# meca_2014.net
KiCad netlist of a schematic drawn in EAGLE
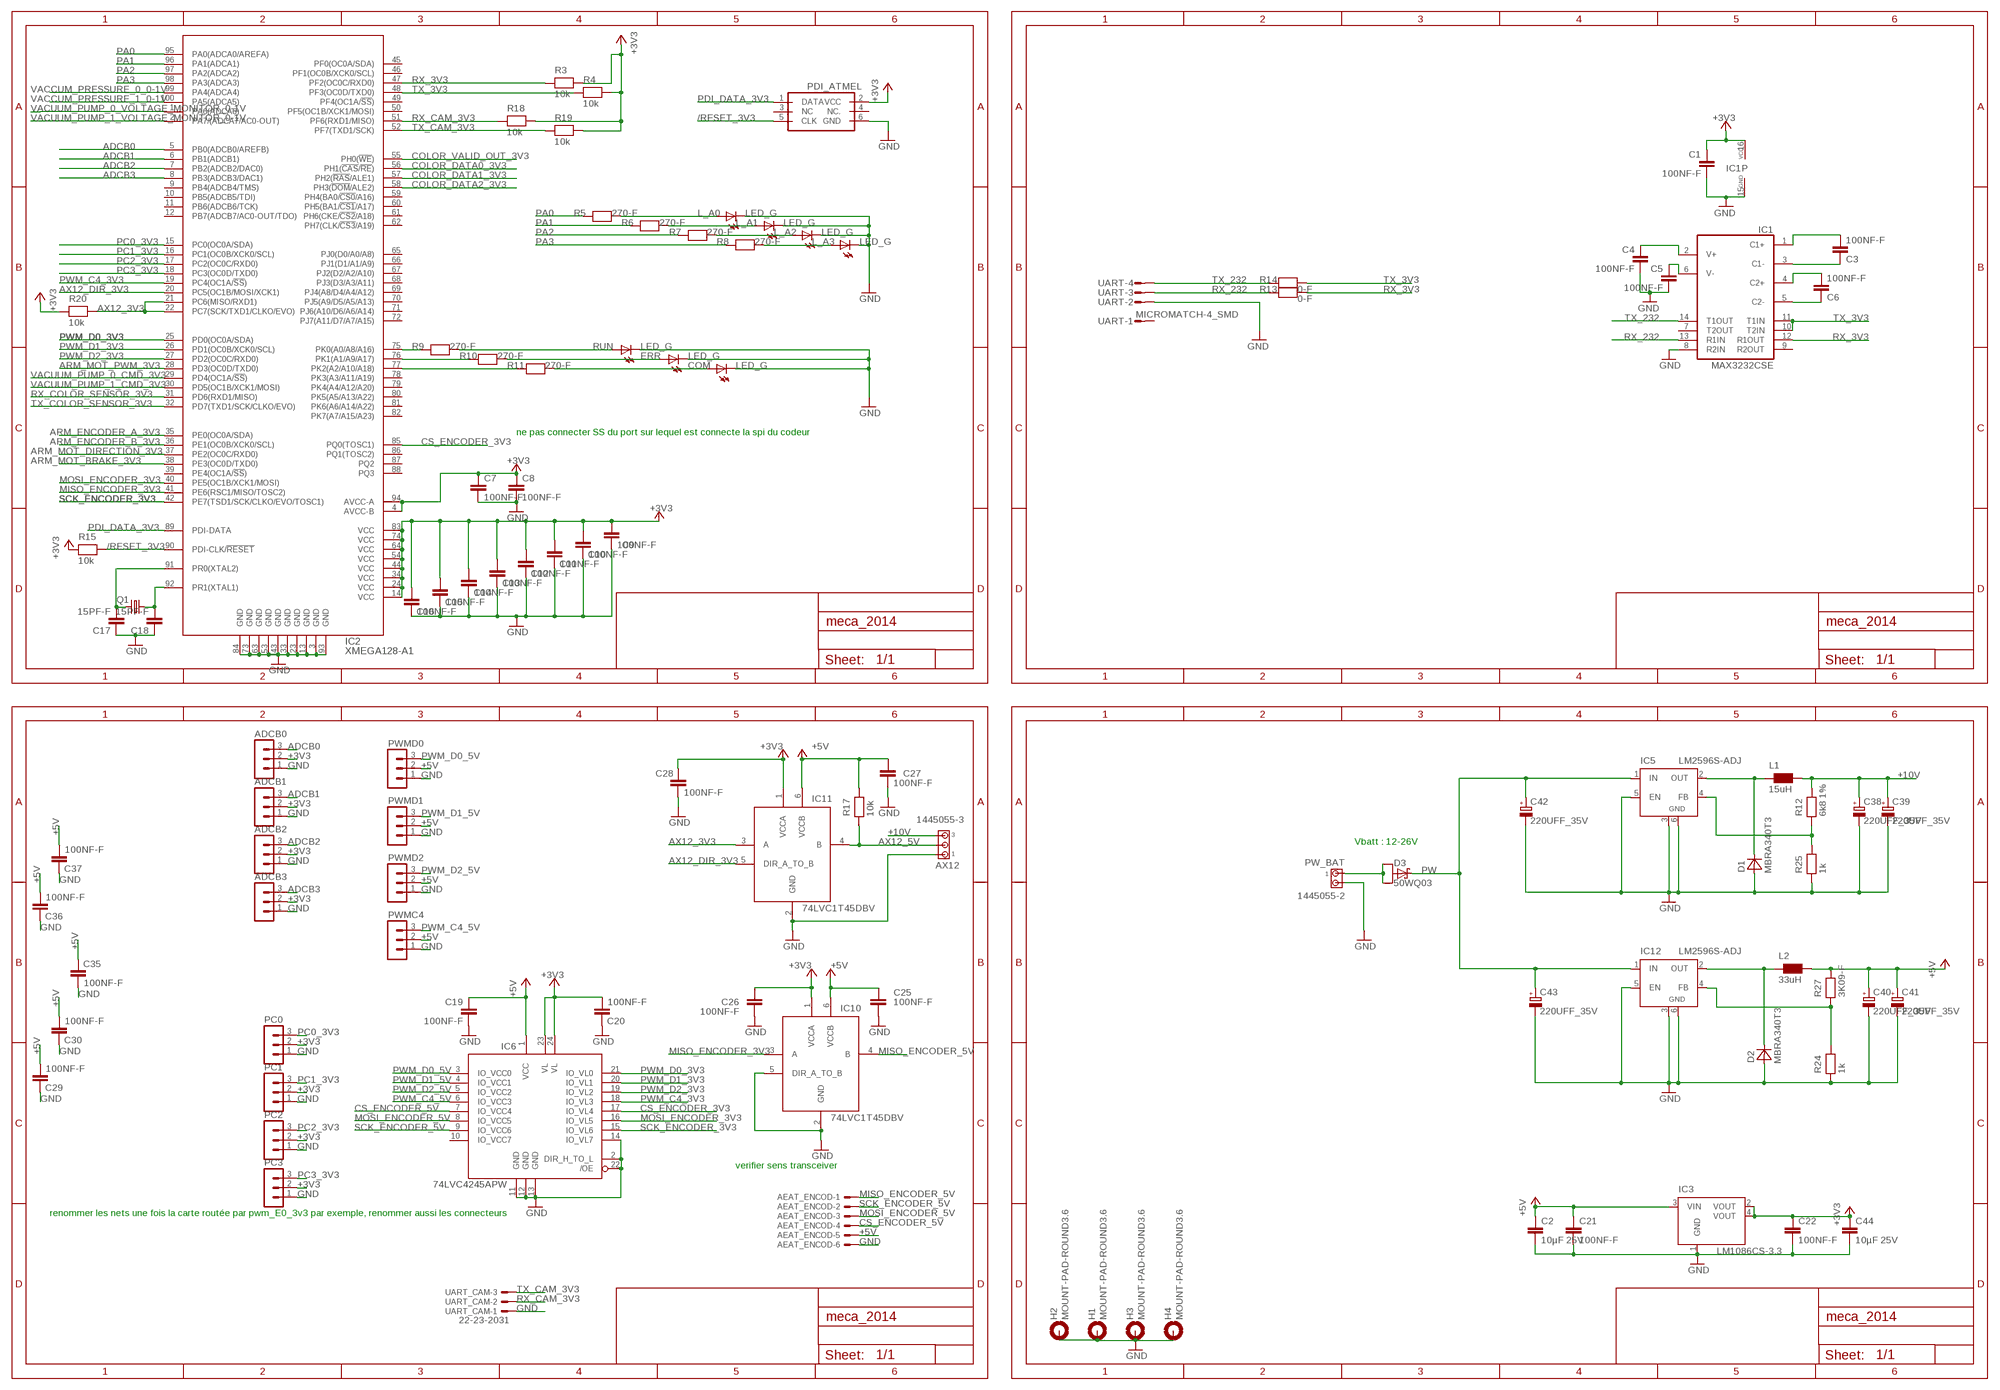
[diagram p0: schematic, sheet 1, part 1 of 2]
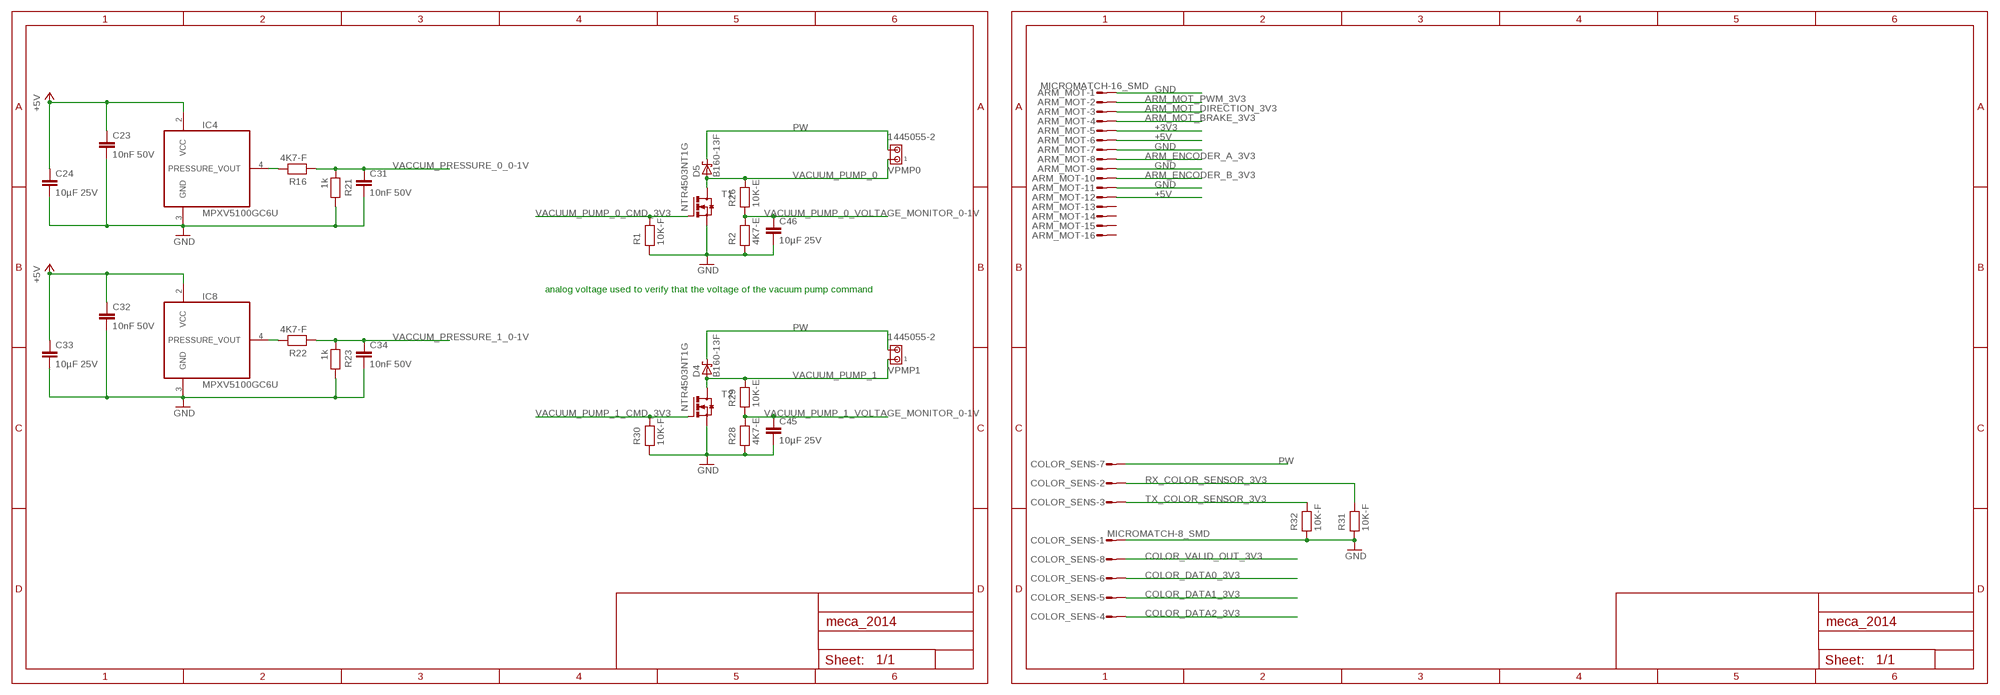
[diagram p1: schematic, sheet 1, part 2 of 2]

(export (version "E")
  (design (tool "Eeschema 10.0.6"))
  (components
    (comp (ref "ADCB0")
      (value "MA03-1")
      (footprint "eagle-import:MA03-1")
      (fields (field (name "OC_FARNELL") "unknown") (field (name "OC_NEWARK") "unknown"))
      (libsource (lib "eagle-import") (part "MA03-1"))
    )
    (comp (ref "ADCB1")
      (value "MA03-1")
      (footprint "eagle-import:MA03-1")
      (fields (field (name "OC_FARNELL") "unknown") (field (name "OC_NEWARK") "unknown"))
      (libsource (lib "eagle-import") (part "MA03-1"))
    )
    (comp (ref "ADCB2")
      (value "MA03-1")
      (footprint "eagle-import:MA03-1")
      (fields (field (name "OC_FARNELL") "unknown") (field (name "OC_NEWARK") "unknown"))
      (libsource (lib "eagle-import") (part "MA03-1"))
    )
    (comp (ref "ADCB3")
      (value "MA03-1")
      (footprint "eagle-import:MA03-1")
      (fields (field (name "OC_FARNELL") "unknown") (field (name "OC_NEWARK") "unknown"))
      (libsource (lib "eagle-import") (part "MA03-1"))
    )
    (comp (ref "AEAT_ENCOD")
      (value "22-23-2061")
      (footprint "eagle-import:22-23-2061")
      (fields (field (name "MF") "MOLEX"))
      (libsource (lib "eagle-import") (part "22-23-2061"))
    )
    (comp (ref "ARM_MOT")
      (value "MICROMATCH-16_SMD")
      (footprint "eagle-import:MICROMATCH-16_SMD")
      (libsource (lib "eagle-import") (part "MICROMATCH-16_SMD"))
    )
    (comp (ref "AX12")
      (value "1445055-3")
      (footprint "eagle-import:1445055-3")
      (libsource (lib "eagle-import") (part "1445055-3"))
    )
    (comp (ref "C1")
      (value "100NF-F")
      (footprint "eagle-import:C0603")
      (libsource (lib "eagle-import") (part "100NF-F"))
    )
    (comp (ref "C2")
      (value "10µF 25V")
      (footprint "eagle-import:C1210")
      (libsource (lib "eagle-import") (part "10UF-C_25V"))
    )
    (comp (ref "C3")
      (value "100NF-F")
      (footprint "eagle-import:C0603")
      (libsource (lib "eagle-import") (part "100NF-F"))
    )
    (comp (ref "C4")
      (value "100NF-F")
      (footprint "eagle-import:C0603")
      (libsource (lib "eagle-import") (part "100NF-F"))
    )
    (comp (ref "C5")
      (value "100NF-F")
      (footprint "eagle-import:C0603")
      (libsource (lib "eagle-import") (part "100NF-F"))
    )
    (comp (ref "C6")
      (value "100NF-F")
      (footprint "eagle-import:C0603")
      (libsource (lib "eagle-import") (part "100NF-F"))
    )
    (comp (ref "C7")
      (value "100NF-F")
      (footprint "eagle-import:C0603")
      (libsource (lib "eagle-import") (part "100NF-F"))
    )
    (comp (ref "C8")
      (value "100NF-F")
      (footprint "eagle-import:C0603")
      (libsource (lib "eagle-import") (part "100NF-F"))
    )
    (comp (ref "C9")
      (value "100NF-F")
      (footprint "eagle-import:C0603")
      (libsource (lib "eagle-import") (part "100NF-F"))
    )
    (comp (ref "C10")
      (value "100NF-F")
      (footprint "eagle-import:C0603")
      (libsource (lib "eagle-import") (part "100NF-F"))
    )
    (comp (ref "C11")
      (value "100NF-F")
      (footprint "eagle-import:C0603")
      (libsource (lib "eagle-import") (part "100NF-F"))
    )
    (comp (ref "C12")
      (value "100NF-F")
      (footprint "eagle-import:C0603")
      (libsource (lib "eagle-import") (part "100NF-F"))
    )
    (comp (ref "C13")
      (value "100NF-F")
      (footprint "eagle-import:C0603")
      (libsource (lib "eagle-import") (part "100NF-F"))
    )
    (comp (ref "C14")
      (value "100NF-F")
      (footprint "eagle-import:C0603")
      (libsource (lib "eagle-import") (part "100NF-F"))
    )
    (comp (ref "C15")
      (value "100NF-F")
      (footprint "eagle-import:C0603")
      (libsource (lib "eagle-import") (part "100NF-F"))
    )
    (comp (ref "C16")
      (value "100NF-F")
      (footprint "eagle-import:C0603")
      (libsource (lib "eagle-import") (part "100NF-F"))
    )
    (comp (ref "C17")
      (value "15PF-F")
      (footprint "eagle-import:C0603")
      (libsource (lib "eagle-import") (part "15PF-F"))
    )
    (comp (ref "C18")
      (value "15PF-F")
      (footprint "eagle-import:C0603")
      (libsource (lib "eagle-import") (part "15PF-F"))
    )
    (comp (ref "C19")
      (value "100NF-F")
      (footprint "eagle-import:C0603")
      (libsource (lib "eagle-import") (part "100NF-F"))
    )
    (comp (ref "C20")
      (value "100NF-F")
      (footprint "eagle-import:C0603")
      (libsource (lib "eagle-import") (part "100NF-F"))
    )
    (comp (ref "C21")
      (value "100NF-F")
      (footprint "eagle-import:C0603")
      (libsource (lib "eagle-import") (part "100NF-F"))
    )
    (comp (ref "C22")
      (value "100NF-F")
      (footprint "eagle-import:C0603")
      (libsource (lib "eagle-import") (part "100NF-F"))
    )
    (comp (ref "C23")
      (value "10nF 50V")
      (footprint "eagle-import:C0603")
      (libsource (lib "eagle-import") (part "10NF-F"))
    )
    (comp (ref "C24")
      (value "10µF 25V")
      (footprint "eagle-import:C1210")
      (libsource (lib "eagle-import") (part "10UF-C_25V"))
    )
    (comp (ref "C25")
      (value "100NF-F")
      (footprint "eagle-import:C0603")
      (libsource (lib "eagle-import") (part "100NF-F"))
    )
    (comp (ref "C26")
      (value "100NF-F")
      (footprint "eagle-import:C0603")
      (libsource (lib "eagle-import") (part "100NF-F"))
    )
    (comp (ref "C27")
      (value "100NF-F")
      (footprint "eagle-import:C0603")
      (libsource (lib "eagle-import") (part "100NF-F"))
    )
    (comp (ref "C28")
      (value "100NF-F")
      (footprint "eagle-import:C0603")
      (libsource (lib "eagle-import") (part "100NF-F"))
    )
    (comp (ref "C29")
      (value "100NF-F")
      (footprint "eagle-import:C0603")
      (libsource (lib "eagle-import") (part "100NF-F"))
    )
    (comp (ref "C30")
      (value "100NF-F")
      (footprint "eagle-import:C0603")
      (libsource (lib "eagle-import") (part "100NF-F"))
    )
    (comp (ref "C31")
      (value "10nF 50V")
      (footprint "eagle-import:C0603")
      (libsource (lib "eagle-import") (part "10NF-F"))
    )
    (comp (ref "C32")
      (value "10nF 50V")
      (footprint "eagle-import:C0603")
      (libsource (lib "eagle-import") (part "10NF-F"))
    )
    (comp (ref "C33")
      (value "10µF 25V")
      (footprint "eagle-import:C1210")
      (libsource (lib "eagle-import") (part "10UF-C_25V"))
    )
    (comp (ref "C34")
      (value "10nF 50V")
      (footprint "eagle-import:C0603")
      (libsource (lib "eagle-import") (part "10NF-F"))
    )
    (comp (ref "C35")
      (value "100NF-F")
      (footprint "eagle-import:C0603")
      (libsource (lib "eagle-import") (part "100NF-F"))
    )
    (comp (ref "C36")
      (value "100NF-F")
      (footprint "eagle-import:C0603")
      (libsource (lib "eagle-import") (part "100NF-F"))
    )
    (comp (ref "C37")
      (value "100NF-F")
      (footprint "eagle-import:C0603")
      (libsource (lib "eagle-import") (part "100NF-F"))
    )
    (comp (ref "C38")
      (value "220UFF_35V")
      (footprint "eagle-import:PANASONIC_F")
      (libsource (lib "eagle-import") (part "220UFF_35V"))
    )
    (comp (ref "C39")
      (value "220UFF_35V")
      (footprint "eagle-import:PANASONIC_F")
      (libsource (lib "eagle-import") (part "220UFF_35V"))
    )
    (comp (ref "C40")
      (value "220UFF_35V")
      (footprint "eagle-import:PANASONIC_F")
      (libsource (lib "eagle-import") (part "220UFF_35V"))
    )
    (comp (ref "C41")
      (value "220UFF_35V")
      (footprint "eagle-import:PANASONIC_F")
      (libsource (lib "eagle-import") (part "220UFF_35V"))
    )
    (comp (ref "C42")
      (value "220UFF_35V")
      (footprint "eagle-import:PANASONIC_F")
      (libsource (lib "eagle-import") (part "220UFF_35V"))
    )
    (comp (ref "C43")
      (value "220UFF_35V")
      (footprint "eagle-import:PANASONIC_F")
      (libsource (lib "eagle-import") (part "220UFF_35V"))
    )
    (comp (ref "C44")
      (value "10µF 25V")
      (footprint "eagle-import:C1210")
      (libsource (lib "eagle-import") (part "10UF-C_25V"))
    )
    (comp (ref "C45")
      (value "10µF 25V")
      (footprint "eagle-import:C1210")
      (libsource (lib "eagle-import") (part "10UF-C_25V"))
    )
    (comp (ref "C46")
      (value "10µF 25V")
      (footprint "eagle-import:C1210")
      (libsource (lib "eagle-import") (part "10UF-C_25V"))
    )
    (comp (ref "COLOR_SENS")
      (value "MICROMATCH-8_SMD")
      (footprint "eagle-import:MICROMATCH-8_SMD")
      (libsource (lib "eagle-import") (part "MICROMATCH-8_SMD"))
    )
    (comp (ref "COM")
      (value "LED_G")
      (footprint "eagle-import:CHIP-LED0805")
      (libsource (lib "eagle-import") (part "LED_G"))
    )
    (comp (ref "D1")
      (value "MBRA340T3")
      (footprint "eagle-import:SMA")
      (libsource (lib "eagle-import") (part "MBRA340T3"))
    )
    (comp (ref "D2")
      (value "MBRA340T3")
      (footprint "eagle-import:SMA")
      (libsource (lib "eagle-import") (part "MBRA340T3"))
    )
    (comp (ref "D3")
      (value "50WQ03")
      (footprint "eagle-import:TO252")
      (libsource (lib "eagle-import") (part "50WQ03"))
    )
    (comp (ref "D4")
      (value "B160-13F")
      (footprint "eagle-import:SMA")
      (libsource (lib "eagle-import") (part "B160-13F"))
    )
    (comp (ref "D5")
      (value "B160-13F")
      (footprint "eagle-import:SMA")
      (libsource (lib "eagle-import") (part "B160-13F"))
    )
    (comp (ref "ERR")
      (value "LED_G")
      (footprint "eagle-import:CHIP-LED0805")
      (libsource (lib "eagle-import") (part "LED_G"))
    )
    (comp (ref "H1")
      (value "MOUNT-PAD-ROUND3.6")
      (footprint "eagle-import:3,6-PAD")
      (libsource (lib "eagle-import") (part "MOUNT-PAD-ROUND3.6"))
    )
    (comp (ref "H2")
      (value "MOUNT-PAD-ROUND3.6")
      (footprint "eagle-import:3,6-PAD")
      (libsource (lib "eagle-import") (part "MOUNT-PAD-ROUND3.6"))
    )
    (comp (ref "H3")
      (value "MOUNT-PAD-ROUND3.6")
      (footprint "eagle-import:3,6-PAD")
      (libsource (lib "eagle-import") (part "MOUNT-PAD-ROUND3.6"))
    )
    (comp (ref "H4")
      (value "MOUNT-PAD-ROUND3.6")
      (footprint "eagle-import:3,6-PAD")
      (libsource (lib "eagle-import") (part "MOUNT-PAD-ROUND3.6"))
    )
    (comp (ref "IC1")
      (value "MAX3232CSE")
      (footprint "eagle-import:SO16")
      (libsource (lib "eagle-import") (part "MAX3232SEC"))
    )
    (comp (ref "IC2")
      (value "XMEGA128-A1")
      (footprint "eagle-import:TQFP100")
      (libsource (lib "eagle-import") (part "XMEGA-A1TQFP"))
    )
    (comp (ref "IC3")
      (value "LM1086CS-3.3")
      (footprint "eagle-import:TO263")
      (libsource (lib "eagle-import") (part "LM1086CS-3.3"))
    )
    (comp (ref "IC4")
      (value "MPXV5100GC6U")
      (footprint "eagle-import:482A")
      (libsource (lib "eagle-import") (part "MPXV5100GC6U"))
    )
    (comp (ref "IC5")
      (value "LM2596S-ADJ")
      (footprint "eagle-import:TO263-5")
      (libsource (lib "eagle-import") (part "LM2596S-ADJ"))
    )
    (comp (ref "IC6")
      (value "74LVC4245APW")
      (footprint "eagle-import:TSSOP24")
      (libsource (lib "eagle-import") (part "74LVC4245APW"))
    )
    (comp (ref "IC8")
      (value "MPXV5100GC6U")
      (footprint "eagle-import:482A")
      (libsource (lib "eagle-import") (part "MPXV5100GC6U"))
    )
    (comp (ref "IC10")
      (value "74LVC1T45DBV")
      (footprint "eagle-import:SOT23-6")
      (libsource (lib "eagle-import") (part "74LVC1T45DBV"))
    )
    (comp (ref "IC11")
      (value "74LVC1T45DBV")
      (footprint "eagle-import:SOT23-6")
      (libsource (lib "eagle-import") (part "74LVC1T45DBV"))
    )
    (comp (ref "IC12")
      (value "LM2596S-ADJ")
      (footprint "eagle-import:TO263-5")
      (libsource (lib "eagle-import") (part "LM2596S-ADJ"))
    )
    (comp (ref "L1")
      (value "15uH")
      (footprint "eagle-import:SRR1280")
      (libsource (lib "eagle-import") (part "SRR1280-150"))
    )
    (comp (ref "L2")
      (value "33uH")
      (footprint "eagle-import:SRR1280")
      (libsource (lib "eagle-import") (part "33µH-3.3A"))
    )
    (comp (ref "L_A0")
      (value "LED_G")
      (footprint "eagle-import:CHIP-LED0805")
      (libsource (lib "eagle-import") (part "LED_G"))
    )
    (comp (ref "L_A1")
      (value "LED_G")
      (footprint "eagle-import:CHIP-LED0805")
      (libsource (lib "eagle-import") (part "LED_G"))
    )
    (comp (ref "L_A2")
      (value "LED_G")
      (footprint "eagle-import:CHIP-LED0805")
      (libsource (lib "eagle-import") (part "LED_G"))
    )
    (comp (ref "L_A3")
      (value "LED_G")
      (footprint "eagle-import:CHIP-LED0805")
      (libsource (lib "eagle-import") (part "LED_G"))
    )
    (comp (ref "PC0")
      (value "MA03-1")
      (footprint "eagle-import:MA03-1")
      (fields (field (name "OC_FARNELL") "unknown") (field (name "OC_NEWARK") "unknown"))
      (libsource (lib "eagle-import") (part "MA03-1"))
    )
    (comp (ref "PC1")
      (value "MA03-1")
      (footprint "eagle-import:MA03-1")
      (fields (field (name "OC_FARNELL") "unknown") (field (name "OC_NEWARK") "unknown"))
      (libsource (lib "eagle-import") (part "MA03-1"))
    )
    (comp (ref "PC2")
      (value "MA03-1")
      (footprint "eagle-import:MA03-1")
      (fields (field (name "OC_FARNELL") "unknown") (field (name "OC_NEWARK") "unknown"))
      (libsource (lib "eagle-import") (part "MA03-1"))
    )
    (comp (ref "PC3")
      (value "MA03-1")
      (footprint "eagle-import:MA03-1")
      (fields (field (name "OC_FARNELL") "unknown") (field (name "OC_NEWARK") "unknown"))
      (libsource (lib "eagle-import") (part "MA03-1"))
    )
    (comp (ref "PDI_ATMEL")
      (value "PDI_ATMELL")
      (footprint "eagle-import:ML6L")
      (libsource (lib "eagle-import") (part "PDI_ATMELL"))
    )
    (comp (ref "PWMC4")
      (value "MA03-1")
      (footprint "eagle-import:MA03-1")
      (libsource (lib "eagle-import") (part "MA03-1"))
    )
    (comp (ref "PWMD0")
      (value "MA03-1")
      (footprint "eagle-import:MA03-1")
      (fields (field (name "OC_FARNELL") "unknown") (field (name "OC_NEWARK") "unknown"))
      (libsource (lib "eagle-import") (part "MA03-1"))
    )
    (comp (ref "PWMD1")
      (value "MA03-1")
      (footprint "eagle-import:MA03-1")
      (fields (field (name "OC_FARNELL") "unknown") (field (name "OC_NEWARK") "unknown"))
      (libsource (lib "eagle-import") (part "MA03-1"))
    )
    (comp (ref "PWMD2")
      (value "MA03-1")
      (footprint "eagle-import:MA03-1")
      (fields (field (name "OC_FARNELL") "unknown") (field (name "OC_NEWARK") "unknown"))
      (libsource (lib "eagle-import") (part "MA03-1"))
    )
    (comp (ref "PW_BAT")
      (value "1445055-2")
      (footprint "eagle-import:1445055-2")
      (libsource (lib "eagle-import") (part "1445055-2"))
    )
    (comp (ref "Q1")
      (value "CRYSTAL_16MHZ_HC49UP")
      (footprint "eagle-import:HC49UP")
      (libsource (lib "eagle-import") (part "CRYSTAL_16MHZ_HC49UP"))
    )
    (comp (ref "R1")
      (value "10K-F")
      (footprint "eagle-import:R0603")
      (libsource (lib "eagle-import") (part "10K-F"))
    )
    (comp (ref "R2")
      (value "4K7-E")
      (footprint "eagle-import:R0805")
      (libsource (lib "eagle-import") (part "4K7-E"))
    )
    (comp (ref "R3")
      (value "10k")
      (footprint "eagle-import:R0603")
      (libsource (lib "eagle-import") (part "10K-F"))
    )
    (comp (ref "R4")
      (value "10k")
      (footprint "eagle-import:R0603")
      (libsource (lib "eagle-import") (part "10K-F"))
    )
    (comp (ref "R5")
      (value "270-F")
      (footprint "eagle-import:R0603")
      (libsource (lib "eagle-import") (part "270-F"))
    )
    (comp (ref "R6")
      (value "270-F")
      (footprint "eagle-import:R0603")
      (libsource (lib "eagle-import") (part "270-F"))
    )
    (comp (ref "R7")
      (value "270-F")
      (footprint "eagle-import:R0603")
      (libsource (lib "eagle-import") (part "270-F"))
    )
    (comp (ref "R8")
      (value "270-F")
      (footprint "eagle-import:R0603")
      (libsource (lib "eagle-import") (part "270-F"))
    )
    (comp (ref "R9")
      (value "270-F")
      (footprint "eagle-import:R0603")
      (libsource (lib "eagle-import") (part "270-F"))
    )
    (comp (ref "R10")
      (value "270-F")
      (footprint "eagle-import:R0603")
      (libsource (lib "eagle-import") (part "270-F"))
    )
    (comp (ref "R11")
      (value "270-F")
      (footprint "eagle-import:R0603")
      (libsource (lib "eagle-import") (part "270-F"))
    )
    (comp (ref "R12")
      (value "6k8 1%")
      (footprint "eagle-import:R0603")
      (libsource (lib "eagle-import") (part "6K8-F"))
    )
    (comp (ref "R13")
      (value "0-F")
      (footprint "eagle-import:R0603")
      (libsource (lib "eagle-import") (part "0-F"))
    )
    (comp (ref "R14")
      (value "0-F")
      (footprint "eagle-import:R0603")
      (libsource (lib "eagle-import") (part "0-F"))
    )
    (comp (ref "R15")
      (value "10k")
      (footprint "eagle-import:R0603")
      (libsource (lib "eagle-import") (part "10K-F"))
    )
    (comp (ref "R16")
      (value "4K7-F")
      (footprint "eagle-import:R0603")
      (libsource (lib "eagle-import") (part "4K7-F"))
    )
    (comp (ref "R17")
      (value "10k")
      (footprint "eagle-import:R0603")
      (libsource (lib "eagle-import") (part "10K-F"))
    )
    (comp (ref "R18")
      (value "10k")
      (footprint "eagle-import:R0603")
      (libsource (lib "eagle-import") (part "10K-F"))
    )
    (comp (ref "R19")
      (value "10k")
      (footprint "eagle-import:R0603")
      (libsource (lib "eagle-import") (part "10K-F"))
    )
    (comp (ref "R20")
      (value "10k")
      (footprint "eagle-import:R0603")
      (libsource (lib "eagle-import") (part "10K-F"))
    )
    (comp (ref "R21")
      (value "1k")
      (footprint "eagle-import:R0603")
      (libsource (lib "eagle-import") (part "1K-F"))
    )
    (comp (ref "R22")
      (value "4K7-F")
      (footprint "eagle-import:R0603")
      (libsource (lib "eagle-import") (part "4K7-F"))
    )
    (comp (ref "R23")
      (value "1k")
      (footprint "eagle-import:R0603")
      (libsource (lib "eagle-import") (part "1K-F"))
    )
    (comp (ref "R24")
      (value "1k")
      (footprint "eagle-import:R0603")
      (libsource (lib "eagle-import") (part "1K-F"))
    )
    (comp (ref "R25")
      (value "1k")
      (footprint "eagle-import:R0603")
      (libsource (lib "eagle-import") (part "1K-F"))
    )
    (comp (ref "R26")
      (value "10K-E")
      (footprint "eagle-import:R0805")
      (libsource (lib "eagle-import") (part "10K-E"))
    )
    (comp (ref "R27")
      (value "3K09-F")
      (footprint "eagle-import:R0603")
      (libsource (lib "eagle-import") (part "3K09-F"))
    )
    (comp (ref "R28")
      (value "4K7-E")
      (footprint "eagle-import:R0805")
      (libsource (lib "eagle-import") (part "4K7-E"))
    )
    (comp (ref "R29")
      (value "10K-E")
      (footprint "eagle-import:R0805")
      (libsource (lib "eagle-import") (part "10K-E"))
    )
    (comp (ref "R30")
      (value "10K-F")
      (footprint "eagle-import:R0603")
      (libsource (lib "eagle-import") (part "10K-F"))
    )
    (comp (ref "R31")
      (value "10K-F")
      (footprint "eagle-import:R0603")
      (libsource (lib "eagle-import") (part "10K-F"))
    )
    (comp (ref "R32")
      (value "10K-F")
      (footprint "eagle-import:R0603")
      (libsource (lib "eagle-import") (part "10K-F"))
    )
    (comp (ref "RUN")
      (value "LED_G")
      (footprint "eagle-import:CHIP-LED0805")
      (libsource (lib "eagle-import") (part "LED_G"))
    )
    (comp (ref "T1")
      (value "NTR4503NT1G")
      (footprint "eagle-import:SOT23")
      (libsource (lib "eagle-import") (part "NTR4503NT1G"))
    )
    (comp (ref "T2")
      (value "NTR4503NT1G")
      (footprint "eagle-import:SOT23")
      (libsource (lib "eagle-import") (part "NTR4503NT1G"))
    )
    (comp (ref "UART")
      (value "MICROMATCH-4_SMD")
      (footprint "eagle-import:MICROMATCH-4_SMD")
      (libsource (lib "eagle-import") (part "MICROMATCH-4_SMD"))
    )
    (comp (ref "UART_CAM")
      (value "22-23-2031")
      (footprint "eagle-import:22-23-2031")
      (fields (field (name "MF") "MOLEX"))
      (libsource (lib "eagle-import") (part "22-23-2031"))
    )
    (comp (ref "VPMP0")
      (value "1445055-2")
      (footprint "eagle-import:1445055-2")
      (libsource (lib "eagle-import") (part "1445055-2"))
    )
    (comp (ref "VPMP1")
      (value "1445055-2")
      (footprint "eagle-import:1445055-2")
      (libsource (lib "eagle-import") (part "1445055-2"))
    )
  )
  (nets
    (net (code "1") (name "+3V3") (class "Default")
      (node (ref "ADCB0") (pin "2") (pinfunction "2_2") (pintype "passive"))
      (node (ref "ADCB1") (pin "2") (pinfunction "2_2") (pintype "passive"))
      (node (ref "ADCB2") (pin "2") (pinfunction "2_2") (pintype "passive"))
      (node (ref "ADCB3") (pin "2") (pinfunction "2_2") (pintype "passive"))
      (node (ref "ARM_MOT") (pin "5") (pinfunction "S_5") (pintype "passive"))
      (node (ref "C1") (pin "1") (pinfunction "1_1") (pintype "passive"))
      (node (ref "C10") (pin "1") (pinfunction "1_1") (pintype "passive"))
      (node (ref "C11") (pin "1") (pinfunction "1_1") (pintype "passive"))
      (node (ref "C12") (pin "1") (pinfunction "1_1") (pintype "passive"))
      (node (ref "C13") (pin "1") (pinfunction "1_1") (pintype "passive"))
      (node (ref "C14") (pin "1") (pinfunction "1_1") (pintype "passive"))
      (node (ref "C15") (pin "1") (pinfunction "1_1") (pintype "passive"))
      (node (ref "C16") (pin "1") (pinfunction "1_1") (pintype "passive"))
      (node (ref "C20") (pin "1") (pinfunction "1_1") (pintype "passive"))
      (node (ref "C22") (pin "1") (pinfunction "1_1") (pintype "passive"))
      (node (ref "C26") (pin "1") (pinfunction "1_1") (pintype "passive"))
      (node (ref "C28") (pin "1") (pinfunction "1_1") (pintype "passive"))
      (node (ref "C44") (pin "1") (pinfunction "1_1") (pintype "passive"))
      (node (ref "C7") (pin "1") (pinfunction "1_1") (pintype "passive"))
      (node (ref "C8") (pin "1") (pinfunction "1_1") (pintype "passive"))
      (node (ref "C9") (pin "1") (pinfunction "1_1") (pintype "passive"))
      (node (ref "IC1") (pin "16") (pinfunction "VCC_16") (pintype "power_in"))
      (node (ref "IC10") (pin "1") (pinfunction "VCCA_1") (pintype "power_in"))
      (node (ref "IC11") (pin "1") (pinfunction "VCCA_1") (pintype "power_in"))
      (node (ref "IC2") (pin "14") (pinfunction "VCC_14") (pintype "power_in"))
      (node (ref "IC2") (pin "24") (pinfunction "VCC_24") (pintype "power_in"))
      (node (ref "IC2") (pin "34") (pinfunction "VCC_34") (pintype "power_in"))
      (node (ref "IC2") (pin "4") (pinfunction "AVCC-B_4") (pintype "power_in"))
      (node (ref "IC2") (pin "44") (pinfunction "VCC_44") (pintype "power_in"))
      (node (ref "IC2") (pin "54") (pinfunction "VCC_54") (pintype "power_in"))
      (node (ref "IC2") (pin "64") (pinfunction "VCC_64") (pintype "power_in"))
      (node (ref "IC2") (pin "74") (pinfunction "VCC_74") (pintype "power_in"))
      (node (ref "IC2") (pin "83") (pinfunction "VCC_83") (pintype "power_in"))
      (node (ref "IC2") (pin "94") (pinfunction "AVCC-A_94") (pintype "power_in"))
      (node (ref "IC3") (pin "2") (pinfunction "VOUT_2") (pintype "bidirectional"))
      (node (ref "IC3") (pin "4") (pinfunction "VOUT_4") (pintype "bidirectional"))
      (node (ref "IC6") (pin "23") (pinfunction "VL_23") (pintype "power_in"))
      (node (ref "IC6") (pin "24") (pinfunction "VL_24") (pintype "power_in"))
      (node (ref "PC0") (pin "2") (pinfunction "2_2") (pintype "passive"))
      (node (ref "PC1") (pin "2") (pinfunction "2_2") (pintype "passive"))
      (node (ref "PC2") (pin "2") (pinfunction "2_2") (pintype "passive"))
      (node (ref "PC3") (pin "2") (pinfunction "2_2") (pintype "passive"))
      (node (ref "PDI_ATMEL") (pin "2") (pinfunction "VCC_2") (pintype "passive"))
      (node (ref "R15") (pin "1") (pinfunction "1_1") (pintype "bidirectional"))
      (node (ref "R18") (pin "2") (pinfunction "2_2") (pintype "bidirectional"))
      (node (ref "R19") (pin "2") (pinfunction "2_2") (pintype "bidirectional"))
      (node (ref "R20") (pin "1") (pinfunction "1_1") (pintype "bidirectional"))
      (node (ref "R3") (pin "2") (pinfunction "2_2") (pintype "bidirectional"))
      (node (ref "R4") (pin "2") (pinfunction "2_2") (pintype "bidirectional"))
    )
    (net (code "2") (name "+5V") (class "Default")
      (node (ref "AEAT_ENCOD") (pin "5") (pinfunction "S_5") (pintype "passive"))
      (node (ref "ARM_MOT") (pin "12") (pinfunction "S_12") (pintype "passive"))
      (node (ref "ARM_MOT") (pin "6") (pinfunction "S_6") (pintype "passive"))
      (node (ref "C19") (pin "1") (pinfunction "1_1") (pintype "passive"))
      (node (ref "C2") (pin "1") (pinfunction "1_1") (pintype "passive"))
      (node (ref "C21") (pin "1") (pinfunction "1_1") (pintype "passive"))
      (node (ref "C23") (pin "1") (pinfunction "1_1") (pintype "passive"))
      (node (ref "C24") (pin "1") (pinfunction "1_1") (pintype "passive"))
      (node (ref "C25") (pin "1") (pinfunction "1_1") (pintype "passive"))
      (node (ref "C27") (pin "1") (pinfunction "1_1") (pintype "passive"))
      (node (ref "C29") (pin "1") (pinfunction "1_1") (pintype "passive"))
      (node (ref "C30") (pin "1") (pinfunction "1_1") (pintype "passive"))
      (node (ref "C32") (pin "1") (pinfunction "1_1") (pintype "passive"))
      (node (ref "C33") (pin "1") (pinfunction "1_1") (pintype "passive"))
      (node (ref "C35") (pin "1") (pinfunction "1_1") (pintype "passive"))
      (node (ref "C36") (pin "1") (pinfunction "1_1") (pintype "passive"))
      (node (ref "C37") (pin "1") (pinfunction "1_1") (pintype "passive"))
      (node (ref "C40") (pin "+") (pinfunction "+_+") (pintype "passive"))
      (node (ref "C41") (pin "+") (pinfunction "+_+") (pintype "passive"))
      (node (ref "IC10") (pin "6") (pinfunction "VCCB_6") (pintype "power_in"))
      (node (ref "IC11") (pin "6") (pinfunction "VCCB_6") (pintype "power_in"))
      (node (ref "IC3") (pin "3") (pinfunction "VIN_3") (pintype "bidirectional"))
      (node (ref "IC4") (pin "2") (pinfunction "VCC_2") (pintype "bidirectional"))
      (node (ref "IC6") (pin "1") (pinfunction "VCC_1") (pintype "power_in"))
      (node (ref "IC8") (pin "2") (pinfunction "VCC_2") (pintype "bidirectional"))
      (node (ref "L2") (pin "2") (pinfunction "2_2") (pintype "passive"))
      (node (ref "PWMC4") (pin "2") (pinfunction "2_2") (pintype "passive"))
      (node (ref "PWMD0") (pin "2") (pinfunction "2_2") (pintype "passive"))
      (node (ref "PWMD1") (pin "2") (pinfunction "2_2") (pintype "passive"))
      (node (ref "PWMD2") (pin "2") (pinfunction "2_2") (pintype "passive"))
      (node (ref "R17") (pin "2") (pinfunction "2_2") (pintype "bidirectional"))
      (node (ref "R27") (pin "2") (pinfunction "2_2") (pintype "bidirectional"))
    )
    (net (code "3") (name "/+10V") (class "Default")
      (node (ref "AX12") (pin "3") (pinfunction "3_3") (pintype "passive"))
      (node (ref "C38") (pin "+") (pinfunction "+_+") (pintype "passive"))
      (node (ref "C39") (pin "+") (pinfunction "+_+") (pintype "passive"))
      (node (ref "L1") (pin "2") (pinfunction "2_2") (pintype "passive"))
      (node (ref "R12") (pin "2") (pinfunction "2_2") (pintype "bidirectional"))
    )
    (net (code "4") (name "/ADCB0") (class "Default")
      (node (ref "ADCB0") (pin "3") (pinfunction "3_3") (pintype "passive"))
      (node (ref "IC2") (pin "5") (pinfunction "PB0(ADCB0/AREFB)_5") (pintype "bidirectional"))
    )
    (net (code "5") (name "/ADCB1") (class "Default")
      (node (ref "ADCB1") (pin "3") (pinfunction "3_3") (pintype "passive"))
      (node (ref "IC2") (pin "6") (pinfunction "PB1(ADCB1)_6") (pintype "bidirectional"))
    )
    (net (code "6") (name "/ADCB2") (class "Default")
      (node (ref "ADCB2") (pin "3") (pinfunction "3_3") (pintype "passive"))
      (node (ref "IC2") (pin "7") (pinfunction "PB2(ADCB2/DAC0)_7") (pintype "bidirectional"))
    )
    (net (code "7") (name "/ADCB3") (class "Default")
      (node (ref "ADCB3") (pin "3") (pinfunction "3_3") (pintype "passive"))
      (node (ref "IC2") (pin "8") (pinfunction "PB3(ADCB3/DAC1)_8") (pintype "bidirectional"))
    )
    (net (code "8") (name "/ARM_ENCODER_A_3V3") (class "Default")
      (node (ref "ARM_MOT") (pin "8") (pinfunction "S_8") (pintype "passive"))
      (node (ref "IC2") (pin "35") (pinfunction "PE0(OC0A/SDA)_35") (pintype "bidirectional"))
    )
    (net (code "9") (name "/ARM_ENCODER_B_3V3") (class "Default")
      (node (ref "ARM_MOT") (pin "10") (pinfunction "S_10") (pintype "passive"))
      (node (ref "IC2") (pin "36") (pinfunction "PE1(OC0B/XCK0/SCL)_36") (pintype "bidirectional"))
    )
    (net (code "10") (name "/ARM_MOT_BRAKE_3V3") (class "Default")
      (node (ref "ARM_MOT") (pin "4") (pinfunction "S_4") (pintype "passive"))
      (node (ref "IC2") (pin "38") (pinfunction "PE3(OC0D/TXD0)_38") (pintype "bidirectional"))
    )
    (net (code "11") (name "/ARM_MOT_DIRECTION_3V3") (class "Default")
      (node (ref "ARM_MOT") (pin "3") (pinfunction "S_3") (pintype "passive"))
      (node (ref "IC2") (pin "37") (pinfunction "PE2(OC0C/RXD0)_37") (pintype "bidirectional"))
    )
    (net (code "12") (name "/ARM_MOT_PWM_3V3") (class "Default")
      (node (ref "ARM_MOT") (pin "2") (pinfunction "S_2") (pintype "passive"))
      (node (ref "IC2") (pin "28") (pinfunction "PD3(OC0D/TXD0)_28") (pintype "bidirectional"))
    )
    (net (code "13") (name "/AX12_3V3") (class "Default")
      (node (ref "IC11") (pin "3") (pinfunction "A_3") (pintype "bidirectional"))
      (node (ref "IC2") (pin "21") (pinfunction "PC6(MISO/RXD1)_21") (pintype "bidirectional"))
      (node (ref "IC2") (pin "22") (pinfunction "PC7(SCK/TXD1/CLKO/EVO)_22") (pintype "bidirectional"))
      (node (ref "R20") (pin "2") (pinfunction "2_2") (pintype "bidirectional"))
    )
    (net (code "14") (name "/AX12_5V") (class "Default")
      (node (ref "AX12") (pin "2") (pinfunction "2_2") (pintype "passive"))
      (node (ref "IC11") (pin "4") (pinfunction "B_4") (pintype "bidirectional"))
      (node (ref "R17") (pin "1") (pinfunction "1_1") (pintype "bidirectional"))
    )
    (net (code "15") (name "/AX12_DIR_3V3") (class "Default")
      (node (ref "IC11") (pin "5") (pinfunction "DIR_A_TO_B_5") (pintype "bidirectional"))
      (node (ref "IC2") (pin "20") (pinfunction "PC5(OC1B/MOSI/XCK1)_20") (pintype "bidirectional"))
    )
    (net (code "16") (name "/COLOR_DATA0_3V3") (class "Default")
      (node (ref "COLOR_SENS") (pin "6") (pinfunction "S_6") (pintype "passive"))
      (node (ref "IC2") (pin "56") (pinfunction "PH1(~{CAS}/~{RE})_56") (pintype "bidirectional"))
    )
    (net (code "17") (name "/COLOR_DATA1_3V3") (class "Default")
      (node (ref "COLOR_SENS") (pin "5") (pinfunction "S_5") (pintype "passive"))
      (node (ref "IC2") (pin "57") (pinfunction "PH2(~{RAS}/ALE1)_57") (pintype "bidirectional"))
    )
    (net (code "18") (name "/COLOR_DATA2_3V3") (class "Default")
      (node (ref "COLOR_SENS") (pin "4") (pinfunction "S_4") (pintype "passive"))
      (node (ref "IC2") (pin "58") (pinfunction "PH3(~{DOM}/ALE2)_58") (pintype "bidirectional"))
    )
    (net (code "19") (name "/COLOR_VALID_OUT_3V3") (class "Default")
      (node (ref "COLOR_SENS") (pin "8") (pinfunction "S_8") (pintype "passive"))
      (node (ref "IC2") (pin "55") (pinfunction "PH0(~{WE})_55") (pintype "bidirectional"))
    )
    (net (code "20") (name "/CS_ENCODER_3V3") (class "Default")
      (node (ref "IC2") (pin "85") (pinfunction "PQ0(TOSC1)_85") (pintype "bidirectional"))
      (node (ref "IC6") (pin "17") (pinfunction "IO_VL4_17") (pintype "bidirectional"))
    )
    (net (code "21") (name "/CS_ENCODER_5V") (class "Default")
      (node (ref "AEAT_ENCOD") (pin "4") (pinfunction "S_4") (pintype "passive"))
      (node (ref "IC6") (pin "7") (pinfunction "IO_VCC4_7") (pintype "bidirectional"))
    )
    (net (code "22") (name "/MISO_ENCODER_3V3") (class "Default")
      (node (ref "IC10") (pin "3") (pinfunction "A_3") (pintype "bidirectional"))
      (node (ref "IC2") (pin "41") (pinfunction "PE6(RSC1/MISO/TOSC2)_41") (pintype "bidirectional"))
    )
    (net (code "23") (name "/MISO_ENCODER_5V") (class "Default")
      (node (ref "AEAT_ENCOD") (pin "1") (pinfunction "S_1") (pintype "passive"))
      (node (ref "IC10") (pin "4") (pinfunction "B_4") (pintype "bidirectional"))
    )
    (net (code "24") (name "/MOSI_ENCODER_3V3") (class "Default")
      (node (ref "IC2") (pin "40") (pinfunction "PE5(OC1B/XCK1/MOSI)_40") (pintype "bidirectional"))
      (node (ref "IC6") (pin "16") (pinfunction "IO_VL5_16") (pintype "bidirectional"))
    )
    (net (code "25") (name "/MOSI_ENCODER_5V") (class "Default")
      (node (ref "AEAT_ENCOD") (pin "3") (pinfunction "S_3") (pintype "passive"))
      (node (ref "IC6") (pin "8") (pinfunction "IO_VCC5_8") (pintype "bidirectional"))
    )
    (net (code "26") (name "/PA0") (class "Default")
      (node (ref "IC2") (pin "95") (pinfunction "PA0(ADCA0/AREFA)_95") (pintype "bidirectional"))
      (node (ref "R5") (pin "1") (pinfunction "1_1") (pintype "bidirectional"))
    )
    (net (code "27") (name "/PA1") (class "Default")
      (node (ref "IC2") (pin "96") (pinfunction "PA1(ADCA1)_96") (pintype "bidirectional"))
      (node (ref "R6") (pin "1") (pinfunction "1_1") (pintype "bidirectional"))
    )
    (net (code "28") (name "/PA2") (class "Default")
      (node (ref "IC2") (pin "97") (pinfunction "PA2(ADCA2)_97") (pintype "bidirectional"))
      (node (ref "R7") (pin "1") (pinfunction "1_1") (pintype "bidirectional"))
    )
    (net (code "29") (name "/PA3") (class "Default")
      (node (ref "IC2") (pin "98") (pinfunction "PA3(ADCA3)_98") (pintype "bidirectional"))
      (node (ref "R8") (pin "1") (pinfunction "1_1") (pintype "bidirectional"))
    )
    (net (code "30") (name "/PC0_3V3") (class "Default")
      (node (ref "IC2") (pin "15") (pinfunction "PC0(OC0A/SDA)_15") (pintype "bidirectional"))
      (node (ref "PC0") (pin "3") (pinfunction "3_3") (pintype "passive"))
    )
    (net (code "31") (name "/PC1_3V3") (class "Default")
      (node (ref "IC2") (pin "16") (pinfunction "PC1(OC0B/XCK0/SCL)_16") (pintype "bidirectional"))
      (node (ref "PC1") (pin "3") (pinfunction "3_3") (pintype "passive"))
    )
    (net (code "32") (name "/PC2_3V3") (class "Default")
      (node (ref "IC2") (pin "17") (pinfunction "PC2(OC0C/RXD0)_17") (pintype "bidirectional"))
      (node (ref "PC2") (pin "3") (pinfunction "3_3") (pintype "passive"))
    )
    (net (code "33") (name "/PC3_3V3") (class "Default")
      (node (ref "IC2") (pin "18") (pinfunction "PC3(OC0D/TXD0)_18") (pintype "bidirectional"))
      (node (ref "PC3") (pin "3") (pinfunction "3_3") (pintype "passive"))
    )
    (net (code "34") (name "/PDI_DATA_3V3") (class "Default")
      (node (ref "IC2") (pin "89") (pinfunction "PDI-DATA_89") (pintype "bidirectional"))
      (node (ref "PDI_ATMEL") (pin "1") (pinfunction "DATA_1") (pintype "passive"))
    )
    (net (code "35") (name "/PW") (class "Default")
      (node (ref "C42") (pin "+") (pinfunction "+_+") (pintype "passive"))
      (node (ref "C43") (pin "+") (pinfunction "+_+") (pintype "passive"))
      (node (ref "COLOR_SENS") (pin "7") (pinfunction "S_7") (pintype "passive"))
      (node (ref "D3") (pin "4") (pinfunction "C_4") (pintype "passive"))
      (node (ref "D4") (pin "A") (pinfunction "C_A") (pintype "passive"))
      (node (ref "D5") (pin "A") (pinfunction "C_A") (pintype "passive"))
      (node (ref "IC12") (pin "1") (pinfunction "IN_1") (pintype "input"))
      (node (ref "IC5") (pin "1") (pinfunction "IN_1") (pintype "input"))
      (node (ref "VPMP0") (pin "2") (pinfunction "2_2") (pintype "passive"))
      (node (ref "VPMP1") (pin "2") (pinfunction "2_2") (pintype "passive"))
    )
    (net (code "36") (name "/PWM_C4_3V3") (class "Default")
      (node (ref "IC2") (pin "19") (pinfunction "PC4(OC1A/~{SS})_19") (pintype "bidirectional"))
      (node (ref "IC6") (pin "18") (pinfunction "IO_VL3_18") (pintype "bidirectional"))
    )
    (net (code "37") (name "/PWM_C4_5V") (class "Default")
      (node (ref "IC6") (pin "6") (pinfunction "IO_VCC3_6") (pintype "bidirectional"))
      (node (ref "PWMC4") (pin "3") (pinfunction "3_3") (pintype "passive"))
    )
    (net (code "38") (name "/PWM_D0_3V3") (class "Default")
      (node (ref "IC2") (pin "25") (pinfunction "PD0(OC0A/SDA)_25") (pintype "bidirectional"))
      (node (ref "IC6") (pin "21") (pinfunction "IO_VL0_21") (pintype "bidirectional"))
    )
    (net (code "39") (name "/PWM_D0_5V") (class "Default")
      (node (ref "IC6") (pin "3") (pinfunction "IO_VCC0_3") (pintype "bidirectional"))
      (node (ref "PWMD0") (pin "3") (pinfunction "3_3") (pintype "passive"))
    )
    (net (code "40") (name "/PWM_D1_3V3") (class "Default")
      (node (ref "IC2") (pin "26") (pinfunction "PD1(OC0B/XCK0/SCL)_26") (pintype "bidirectional"))
      (node (ref "IC6") (pin "20") (pinfunction "IO_VL1_20") (pintype "bidirectional"))
    )
    (net (code "41") (name "/PWM_D1_5V") (class "Default")
      (node (ref "IC6") (pin "4") (pinfunction "IO_VCC1_4") (pintype "bidirectional"))
      (node (ref "PWMD1") (pin "3") (pinfunction "3_3") (pintype "passive"))
    )
    (net (code "42") (name "/PWM_D2_3V3") (class "Default")
      (node (ref "IC2") (pin "27") (pinfunction "PD2(OC0C/RXD0)_27") (pintype "bidirectional"))
      (node (ref "IC6") (pin "19") (pinfunction "IO_VL2_19") (pintype "bidirectional"))
    )
    (net (code "43") (name "/PWM_D2_5V") (class "Default")
      (node (ref "IC6") (pin "5") (pinfunction "IO_VCC2_5") (pintype "bidirectional"))
      (node (ref "PWMD2") (pin "3") (pinfunction "3_3") (pintype "passive"))
    )
    (net (code "44") (name "/RX_3V3") (class "Default")
      (node (ref "IC1") (pin "12") (pinfunction "R1OUT_12") (pintype "output"))
      (node (ref "IC2") (pin "47") (pinfunction "PF2(OC0C/RXD0)_47") (pintype "bidirectional"))
      (node (ref "R13") (pin "2") (pinfunction "2_2") (pintype "bidirectional"))
      (node (ref "R3") (pin "1") (pinfunction "1_1") (pintype "bidirectional"))
    )
    (net (code "45") (name "/RX_232") (class "Default")
      (node (ref "IC1") (pin "13") (pinfunction "R1IN_13") (pintype "input"))
      (node (ref "R13") (pin "1") (pinfunction "1_1") (pintype "bidirectional"))
      (node (ref "UART") (pin "3") (pinfunction "S_3") (pintype "passive"))
    )
    (net (code "46") (name "/RX_CAM_3V3") (class "Default")
      (node (ref "IC2") (pin "51") (pinfunction "PF6(RXD1/MISO)_51") (pintype "bidirectional"))
      (node (ref "R18") (pin "1") (pinfunction "1_1") (pintype "bidirectional"))
      (node (ref "UART_CAM") (pin "2") (pinfunction "S_2") (pintype "passive"))
    )
    (net (code "47") (name "/RX_COLOR_SENSOR_3V3") (class "Default")
      (node (ref "COLOR_SENS") (pin "2") (pinfunction "S_2") (pintype "passive"))
      (node (ref "IC2") (pin "31") (pinfunction "PD6(RXD1/MISO)_31") (pintype "bidirectional"))
      (node (ref "R31") (pin "2") (pinfunction "2_2") (pintype "bidirectional"))
    )
    (net (code "48") (name "/SCK_ENCODER_3V3") (class "Default")
      (node (ref "IC2") (pin "42") (pinfunction "PE7(TSD1/SCK/CLKO/EVO/TOSC1)_42") (pintype "bidirectional"))
      (node (ref "IC6") (pin "15") (pinfunction "IO_VL6_15") (pintype "bidirectional"))
    )
    (net (code "49") (name "/SCK_ENCODER_5V") (class "Default")
      (node (ref "AEAT_ENCOD") (pin "2") (pinfunction "S_2") (pintype "passive"))
      (node (ref "IC6") (pin "9") (pinfunction "IO_VCC6_9") (pintype "bidirectional"))
    )
    (net (code "50") (name "/TX_3V3") (class "Default")
      (node (ref "IC1") (pin "10") (pinfunction "T2IN_10") (pintype "input"))
      (node (ref "IC1") (pin "11") (pinfunction "T1IN_11") (pintype "input"))
      (node (ref "IC2") (pin "48") (pinfunction "PF3(OC0D/TXD0)_48") (pintype "bidirectional"))
      (node (ref "R14") (pin "2") (pinfunction "2_2") (pintype "bidirectional"))
      (node (ref "R4") (pin "1") (pinfunction "1_1") (pintype "bidirectional"))
    )
    (net (code "51") (name "/TX_232") (class "Default")
      (node (ref "IC1") (pin "14") (pinfunction "T1OUT_14") (pintype "output"))
      (node (ref "R14") (pin "1") (pinfunction "1_1") (pintype "bidirectional"))
      (node (ref "UART") (pin "4") (pinfunction "S_4") (pintype "passive"))
    )
    (net (code "52") (name "/TX_CAM_3V3") (class "Default")
      (node (ref "IC2") (pin "52") (pinfunction "PF7(TXD1/SCK)_52") (pintype "bidirectional"))
      (node (ref "R19") (pin "1") (pinfunction "1_1") (pintype "bidirectional"))
      (node (ref "UART_CAM") (pin "3") (pinfunction "S_3") (pintype "passive"))
    )
    (net (code "53") (name "/TX_COLOR_SENSOR_3V3") (class "Default")
      (node (ref "COLOR_SENS") (pin "3") (pinfunction "S_3") (pintype "passive"))
      (node (ref "IC2") (pin "32") (pinfunction "PD7(TXD1/SCK/CLKO/EVO)_32") (pintype "bidirectional"))
      (node (ref "R32") (pin "2") (pinfunction "2_2") (pintype "bidirectional"))
    )
    (net (code "54") (name "/VACCUM_PRESSURE_0_0-1V") (class "Default")
      (node (ref "C31") (pin "1") (pinfunction "1_1") (pintype "passive"))
      (node (ref "IC2") (pin "99") (pinfunction "PA4(ADCA4)_99") (pintype "bidirectional"))
      (node (ref "R16") (pin "1") (pinfunction "1_1") (pintype "bidirectional"))
      (node (ref "R21") (pin "1") (pinfunction "1_1") (pintype "bidirectional"))
    )
    (net (code "55") (name "/VACCUM_PRESSURE_1_0-1V") (class "Default")
      (node (ref "C34") (pin "1") (pinfunction "1_1") (pintype "passive"))
      (node (ref "IC2") (pin "100") (pinfunction "PA5(ADCA5)_100") (pintype "bidirectional"))
      (node (ref "R22") (pin "1") (pinfunction "1_1") (pintype "bidirectional"))
      (node (ref "R23") (pin "1") (pinfunction "1_1") (pintype "bidirectional"))
    )
    (net (code "56") (name "/VACUUM_PUMP_0") (class "Default")
      (node (ref "D5") (pin "C") (pinfunction "A_C") (pintype "passive"))
      (node (ref "R26") (pin "2") (pinfunction "2_2") (pintype "bidirectional"))
      (node (ref "T1") (pin "3") (pinfunction "D_3") (pintype "passive"))
      (node (ref "VPMP0") (pin "1") (pinfunction "1_1") (pintype "passive"))
    )
    (net (code "57") (name "/VACUUM_PUMP_0_CMD_3V3") (class "Default")
      (node (ref "IC2") (pin "29") (pinfunction "PD4(OC1A/~{SS})_29") (pintype "bidirectional"))
      (node (ref "R1") (pin "2") (pinfunction "2_2") (pintype "bidirectional"))
      (node (ref "T1") (pin "1") (pinfunction "G_1") (pintype "passive"))
    )
    (net (code "58") (name "/VACUUM_PUMP_0_VOLTAGE_MONITOR_0-1V") (class "Default")
      (node (ref "C46") (pin "1") (pinfunction "1_1") (pintype "passive"))
      (node (ref "IC2") (pin "1") (pinfunction "PA6(ADCA6)_1") (pintype "bidirectional"))
      (node (ref "R2") (pin "2") (pinfunction "2_2") (pintype "bidirectional"))
      (node (ref "R26") (pin "1") (pinfunction "1_1") (pintype "bidirectional"))
    )
    (net (code "59") (name "/VACUUM_PUMP_1") (class "Default")
      (node (ref "D4") (pin "C") (pinfunction "A_C") (pintype "passive"))
      (node (ref "R29") (pin "2") (pinfunction "2_2") (pintype "bidirectional"))
      (node (ref "T2") (pin "3") (pinfunction "D_3") (pintype "passive"))
      (node (ref "VPMP1") (pin "1") (pinfunction "1_1") (pintype "passive"))
    )
    (net (code "60") (name "/VACUUM_PUMP_1_CMD_3V3") (class "Default")
      (node (ref "IC2") (pin "30") (pinfunction "PD5(OC1B/XCK1/MOSI)_30") (pintype "bidirectional"))
      (node (ref "R30") (pin "2") (pinfunction "2_2") (pintype "bidirectional"))
      (node (ref "T2") (pin "1") (pinfunction "G_1") (pintype "passive"))
    )
    (net (code "61") (name "/VACUUM_PUMP_1_VOLTAGE_MONITOR_0-1V") (class "Default")
      (node (ref "C45") (pin "1") (pinfunction "1_1") (pintype "passive"))
      (node (ref "IC2") (pin "2") (pinfunction "PA7/(ADCA7/AC0-OUT)_2") (pintype "bidirectional"))
      (node (ref "R28") (pin "2") (pinfunction "2_2") (pintype "bidirectional"))
      (node (ref "R29") (pin "1") (pinfunction "1_1") (pintype "bidirectional"))
    )
    (net (code "62") (name "/{slash}RESET_3V3") (class "Default")
      (node (ref "IC2") (pin "90") (pinfunction "PDI-CLK/~{RESET}_90") (pintype "input"))
      (node (ref "PDI_ATMEL") (pin "5") (pinfunction "CLK_5") (pintype "passive"))
      (node (ref "R15") (pin "2") (pinfunction "2_2") (pintype "bidirectional"))
    )
    (net (code "63") (name "GND") (class "Default")
      (node (ref "ADCB0") (pin "1") (pinfunction "1_1") (pintype "passive"))
      (node (ref "ADCB1") (pin "1") (pinfunction "1_1") (pintype "passive"))
      (node (ref "ADCB2") (pin "1") (pinfunction "1_1") (pintype "passive"))
      (node (ref "ADCB3") (pin "1") (pinfunction "1_1") (pintype "passive"))
      (node (ref "AEAT_ENCOD") (pin "6") (pinfunction "S_6") (pintype "passive"))
      (node (ref "ARM_MOT") (pin "1") (pinfunction "S_1") (pintype "passive"))
      (node (ref "ARM_MOT") (pin "11") (pinfunction "S_11") (pintype "passive"))
      (node (ref "ARM_MOT") (pin "7") (pinfunction "S_7") (pintype "passive"))
      (node (ref "ARM_MOT") (pin "9") (pinfunction "S_9") (pintype "passive"))
      (node (ref "AX12") (pin "1") (pinfunction "1_1") (pintype "passive"))
      (node (ref "C1") (pin "2") (pinfunction "2_2") (pintype "passive"))
      (node (ref "C10") (pin "2") (pinfunction "2_2") (pintype "passive"))
      (node (ref "C11") (pin "2") (pinfunction "2_2") (pintype "passive"))
      (node (ref "C12") (pin "2") (pinfunction "2_2") (pintype "passive"))
      (node (ref "C13") (pin "2") (pinfunction "2_2") (pintype "passive"))
      (node (ref "C14") (pin "2") (pinfunction "2_2") (pintype "passive"))
      (node (ref "C15") (pin "2") (pinfunction "2_2") (pintype "passive"))
      (node (ref "C16") (pin "2") (pinfunction "2_2") (pintype "passive"))
      (node (ref "C17") (pin "1") (pinfunction "1_1") (pintype "passive"))
      (node (ref "C18") (pin "1") (pinfunction "1_1") (pintype "passive"))
      (node (ref "C19") (pin "2") (pinfunction "2_2") (pintype "passive"))
      (node (ref "C2") (pin "2") (pinfunction "2_2") (pintype "passive"))
      (node (ref "C20") (pin "2") (pinfunction "2_2") (pintype "passive"))
      (node (ref "C21") (pin "2") (pinfunction "2_2") (pintype "passive"))
      (node (ref "C22") (pin "2") (pinfunction "2_2") (pintype "passive"))
      (node (ref "C23") (pin "2") (pinfunction "2_2") (pintype "passive"))
      (node (ref "C24") (pin "2") (pinfunction "2_2") (pintype "passive"))
      (node (ref "C25") (pin "2") (pinfunction "2_2") (pintype "passive"))
      (node (ref "C26") (pin "2") (pinfunction "2_2") (pintype "passive"))
      (node (ref "C27") (pin "2") (pinfunction "2_2") (pintype "passive"))
      (node (ref "C28") (pin "2") (pinfunction "2_2") (pintype "passive"))
      (node (ref "C29") (pin "2") (pinfunction "2_2") (pintype "passive"))
      (node (ref "C30") (pin "2") (pinfunction "2_2") (pintype "passive"))
      (node (ref "C31") (pin "2") (pinfunction "2_2") (pintype "passive"))
      (node (ref "C32") (pin "2") (pinfunction "2_2") (pintype "passive"))
      (node (ref "C33") (pin "2") (pinfunction "2_2") (pintype "passive"))
      (node (ref "C34") (pin "2") (pinfunction "2_2") (pintype "passive"))
      (node (ref "C35") (pin "2") (pinfunction "2_2") (pintype "passive"))
      (node (ref "C36") (pin "2") (pinfunction "2_2") (pintype "passive"))
      (node (ref "C37") (pin "2") (pinfunction "2_2") (pintype "passive"))
      (node (ref "C38") (pin "-") (pinfunction "-_-") (pintype "passive"))
      (node (ref "C39") (pin "-") (pinfunction "-_-") (pintype "passive"))
      (node (ref "C4") (pin "2") (pinfunction "2_2") (pintype "passive"))
      (node (ref "C40") (pin "-") (pinfunction "-_-") (pintype "passive"))
      (node (ref "C41") (pin "-") (pinfunction "-_-") (pintype "passive"))
      (node (ref "C42") (pin "-") (pinfunction "-_-") (pintype "passive"))
      (node (ref "C43") (pin "-") (pinfunction "-_-") (pintype "passive"))
      (node (ref "C44") (pin "2") (pinfunction "2_2") (pintype "passive"))
      (node (ref "C45") (pin "2") (pinfunction "2_2") (pintype "passive"))
      (node (ref "C46") (pin "2") (pinfunction "2_2") (pintype "passive"))
      (node (ref "C5") (pin "2") (pinfunction "2_2") (pintype "passive"))
      (node (ref "C7") (pin "2") (pinfunction "2_2") (pintype "passive"))
      (node (ref "C8") (pin "2") (pinfunction "2_2") (pintype "passive"))
      (node (ref "C9") (pin "2") (pinfunction "2_2") (pintype "passive"))
      (node (ref "COLOR_SENS") (pin "1") (pinfunction "S_1") (pintype "passive"))
      (node (ref "COM") (pin "C") (pinfunction "C_C") (pintype "passive"))
      (node (ref "D1") (pin "A") (pinfunction "A_A") (pintype "passive"))
      (node (ref "D2") (pin "A") (pinfunction "A_A") (pintype "passive"))
      (node (ref "ERR") (pin "C") (pinfunction "C_C") (pintype "passive"))
      (node (ref "H1") (pin "B3,6") (pinfunction "MOUNT_B3,6") (pintype "passive"))
      (node (ref "H2") (pin "B3,6") (pinfunction "MOUNT_B3,6") (pintype "passive"))
      (node (ref "H3") (pin "B3,6") (pinfunction "MOUNT_B3,6") (pintype "passive"))
      (node (ref "H4") (pin "B3,6") (pinfunction "MOUNT_B3,6") (pintype "passive"))
      (node (ref "IC1") (pin "15") (pinfunction "GND_15") (pintype "power_in"))
      (node (ref "IC1") (pin "8") (pinfunction "R2IN_8") (pintype "input"))
      (node (ref "IC10") (pin "2") (pinfunction "GND_2") (pintype "power_in"))
      (node (ref "IC10") (pin "5") (pinfunction "DIR_A_TO_B_5") (pintype "bidirectional"))
      (node (ref "IC11") (pin "2") (pinfunction "GND_2") (pintype "power_in"))
      (node (ref "IC12") (pin "3") (pinfunction "GND_3") (pintype "power_in"))
      (node (ref "IC12") (pin "5") (pinfunction "EN_5") (pintype "input"))
      (node (ref "IC12") (pin "6") (pinfunction "GND_6") (pintype "power_in"))
      (node (ref "IC2") (pin "13") (pinfunction "GND_13") (pintype "power_in"))
      (node (ref "IC2") (pin "23") (pinfunction "GND_23") (pintype "power_in"))
      (node (ref "IC2") (pin "3") (pinfunction "GND_3") (pintype "power_in"))
      (node (ref "IC2") (pin "33") (pinfunction "GND_33") (pintype "power_in"))
      (node (ref "IC2") (pin "43") (pinfunction "GND_43") (pintype "power_in"))
      (node (ref "IC2") (pin "53") (pinfunction "GND_53") (pintype "power_in"))
      (node (ref "IC2") (pin "63") (pinfunction "GND_63") (pintype "power_in"))
      (node (ref "IC2") (pin "73") (pinfunction "GND_73") (pintype "power_in"))
      (node (ref "IC2") (pin "84") (pinfunction "GND_84") (pintype "power_in"))
      (node (ref "IC2") (pin "93") (pinfunction "GND_93") (pintype "power_in"))
      (node (ref "IC3") (pin "1") (pinfunction "GND_1") (pintype "bidirectional"))
      (node (ref "IC4") (pin "3") (pinfunction "GND_3") (pintype "input"))
      (node (ref "IC5") (pin "3") (pinfunction "GND_3") (pintype "power_in"))
      (node (ref "IC5") (pin "5") (pinfunction "EN_5") (pintype "input"))
      (node (ref "IC5") (pin "6") (pinfunction "GND_6") (pintype "power_in"))
      (node (ref "IC6") (pin "11") (pinfunction "GND_11") (pintype "power_in"))
      (node (ref "IC6") (pin "12") (pinfunction "GND_12") (pintype "power_in"))
      (node (ref "IC6") (pin "13") (pinfunction "GND_13") (pintype "power_in"))
      (node (ref "IC6") (pin "14") (pinfunction "IO_VL7_14") (pintype "bidirectional"))
      (node (ref "IC6") (pin "2") (pinfunction "DIR_H_TO_L_2") (pintype "bidirectional"))
      (node (ref "IC6") (pin "22") (pinfunction "/OE_22") (pintype "bidirectional"))
      (node (ref "IC8") (pin "3") (pinfunction "GND_3") (pintype "input"))
      (node (ref "L_A0") (pin "C") (pinfunction "C_C") (pintype "passive"))
      (node (ref "L_A1") (pin "C") (pinfunction "C_C") (pintype "passive"))
      (node (ref "L_A2") (pin "C") (pinfunction "C_C") (pintype "passive"))
      (node (ref "L_A3") (pin "C") (pinfunction "C_C") (pintype "passive"))
      (node (ref "PC0") (pin "1") (pinfunction "1_1") (pintype "passive"))
      (node (ref "PC1") (pin "1") (pinfunction "1_1") (pintype "passive"))
      (node (ref "PC2") (pin "1") (pinfunction "1_1") (pintype "passive"))
      (node (ref "PC3") (pin "1") (pinfunction "1_1") (pintype "passive"))
      (node (ref "PDI_ATMEL") (pin "6") (pinfunction "GND_6") (pintype "passive"))
      (node (ref "PWMC4") (pin "1") (pinfunction "1_1") (pintype "passive"))
      (node (ref "PWMD0") (pin "1") (pinfunction "1_1") (pintype "passive"))
      (node (ref "PWMD1") (pin "1") (pinfunction "1_1") (pintype "passive"))
      (node (ref "PWMD2") (pin "1") (pinfunction "1_1") (pintype "passive"))
      (node (ref "PW_BAT") (pin "2") (pinfunction "2_2") (pintype "passive"))
      (node (ref "R1") (pin "1") (pinfunction "1_1") (pintype "bidirectional"))
      (node (ref "R2") (pin "1") (pinfunction "1_1") (pintype "bidirectional"))
      (node (ref "R21") (pin "2") (pinfunction "2_2") (pintype "bidirectional"))
      (node (ref "R23") (pin "2") (pinfunction "2_2") (pintype "bidirectional"))
      (node (ref "R24") (pin "1") (pinfunction "1_1") (pintype "bidirectional"))
      (node (ref "R25") (pin "1") (pinfunction "1_1") (pintype "bidirectional"))
      (node (ref "R28") (pin "1") (pinfunction "1_1") (pintype "bidirectional"))
      (node (ref "R30") (pin "1") (pinfunction "1_1") (pintype "bidirectional"))
      (node (ref "R31") (pin "1") (pinfunction "1_1") (pintype "bidirectional"))
      (node (ref "R32") (pin "1") (pinfunction "1_1") (pintype "bidirectional"))
      (node (ref "RUN") (pin "C") (pinfunction "C_C") (pintype "passive"))
      (node (ref "T1") (pin "2") (pinfunction "S_2") (pintype "passive"))
      (node (ref "T2") (pin "2") (pinfunction "S_2") (pintype "passive"))
      (node (ref "UART") (pin "2") (pinfunction "S_2") (pintype "passive"))
      (node (ref "UART_CAM") (pin "1") (pinfunction "S_1") (pintype "passive"))
    )
    (net (code "64") (name "Net-(COM-PadA)") (class "Default")
      (node (ref "COM") (pin "A") (pinfunction "A_A") (pintype "passive"))
      (node (ref "R11") (pin "2") (pinfunction "2_2") (pintype "bidirectional"))
    )
    (net (code "65") (name "Net-(D3-A1)") (class "Default")
      (node (ref "D3") (pin "1") (pinfunction "A1_1") (pintype "passive"))
      (node (ref "D3") (pin "3") (pinfunction "A2_3") (pintype "passive"))
      (node (ref "PW_BAT") (pin "1") (pinfunction "1_1") (pintype "passive"))
    )
    (net (code "66") (name "Net-(ERR-PadA)") (class "Default")
      (node (ref "ERR") (pin "A") (pinfunction "A_A") (pintype "passive"))
      (node (ref "R10") (pin "2") (pinfunction "2_2") (pintype "bidirectional"))
    )
    (net (code "67") (name "Net-(IC1A-C1+)") (class "Default")
      (node (ref "C3") (pin "1") (pinfunction "1_1") (pintype "passive"))
      (node (ref "IC1") (pin "1") (pinfunction "C1+_1") (pintype "bidirectional"))
    )
    (net (code "68") (name "Net-(IC1A-C1-)") (class "Default")
      (node (ref "C3") (pin "2") (pinfunction "2_2") (pintype "passive"))
      (node (ref "IC1") (pin "3") (pinfunction "C1-_3") (pintype "bidirectional"))
    )
    (net (code "69") (name "Net-(IC1A-C2+)") (class "Default")
      (node (ref "C6") (pin "1") (pinfunction "1_1") (pintype "passive"))
      (node (ref "IC1") (pin "4") (pinfunction "C2+_4") (pintype "bidirectional"))
    )
    (net (code "70") (name "Net-(IC1A-C2-)") (class "Default")
      (node (ref "C6") (pin "2") (pinfunction "2_2") (pintype "passive"))
      (node (ref "IC1") (pin "5") (pinfunction "C2-_5") (pintype "bidirectional"))
    )
    (net (code "71") (name "Net-(IC1A-V+)") (class "Default")
      (node (ref "C4") (pin "1") (pinfunction "1_1") (pintype "passive"))
      (node (ref "IC1") (pin "2") (pinfunction "V+_2") (pintype "bidirectional"))
    )
    (net (code "72") (name "Net-(IC1A-V-)") (class "Default")
      (node (ref "C5") (pin "1") (pinfunction "1_1") (pintype "passive"))
      (node (ref "IC1") (pin "6") (pinfunction "V-_6") (pintype "bidirectional"))
    )
    (net (code "73") (name "Net-(IC2-PK0(A0{slash}A8{slash}A16))") (class "Default")
      (node (ref "IC2") (pin "75") (pinfunction "PK0(A0/A8/A16)_75") (pintype "bidirectional"))
      (node (ref "R9") (pin "1") (pinfunction "1_1") (pintype "bidirectional"))
    )
    (net (code "74") (name "Net-(IC2-PK1(A1{slash}A9{slash}A17))") (class "Default")
      (node (ref "IC2") (pin "76") (pinfunction "PK1(A1/A9/A17)_76") (pintype "bidirectional"))
      (node (ref "R10") (pin "1") (pinfunction "1_1") (pintype "bidirectional"))
    )
    (net (code "75") (name "Net-(IC2-PK2(A2{slash}A10{slash}A18))") (class "Default")
      (node (ref "IC2") (pin "77") (pinfunction "PK2(A2/A10/A18)_77") (pintype "bidirectional"))
      (node (ref "R11") (pin "1") (pinfunction "1_1") (pintype "bidirectional"))
    )
    (net (code "76") (name "Net-(IC2-PR0(XTAL2))") (class "Default")
      (node (ref "C17") (pin "2") (pinfunction "2_2") (pintype "passive"))
      (node (ref "IC2") (pin "91") (pinfunction "PR0(XTAL2)_91") (pintype "bidirectional"))
      (node (ref "Q1") (pin "2") (pinfunction "2_2") (pintype "passive"))
    )
    (net (code "77") (name "Net-(IC2-PR1(XTAL1))") (class "Default")
      (node (ref "C18") (pin "2") (pinfunction "2_2") (pintype "passive"))
      (node (ref "IC2") (pin "92") (pinfunction "PR1(XTAL1)_92") (pintype "bidirectional"))
      (node (ref "Q1") (pin "1") (pinfunction "1_1") (pintype "passive"))
    )
    (net (code "78") (name "Net-(IC4-PRESSURE_VOUT)") (class "Default")
      (node (ref "IC4") (pin "4") (pinfunction "PRESSURE_VOUT_4") (pintype "input"))
      (node (ref "R16") (pin "2") (pinfunction "2_2") (pintype "bidirectional"))
    )
    (net (code "79") (name "Net-(IC5-FB)") (class "Default")
      (node (ref "IC5") (pin "4") (pinfunction "FB_4") (pintype "input"))
      (node (ref "R12") (pin "1") (pinfunction "1_1") (pintype "bidirectional"))
      (node (ref "R25") (pin "2") (pinfunction "2_2") (pintype "bidirectional"))
    )
    (net (code "80") (name "Net-(IC5-OUT)") (class "Default")
      (node (ref "D1") (pin "C") (pinfunction "C_C") (pintype "passive"))
      (node (ref "IC5") (pin "2") (pinfunction "OUT_2") (pintype "output"))
      (node (ref "L1") (pin "1") (pinfunction "1_1") (pintype "passive"))
    )
    (net (code "81") (name "Net-(IC8-PRESSURE_VOUT)") (class "Default")
      (node (ref "IC8") (pin "4") (pinfunction "PRESSURE_VOUT_4") (pintype "input"))
      (node (ref "R22") (pin "2") (pinfunction "2_2") (pintype "bidirectional"))
    )
    (net (code "82") (name "Net-(IC12-FB)") (class "Default")
      (node (ref "IC12") (pin "4") (pinfunction "FB_4") (pintype "input"))
      (node (ref "R24") (pin "2") (pinfunction "2_2") (pintype "bidirectional"))
      (node (ref "R27") (pin "1") (pinfunction "1_1") (pintype "bidirectional"))
    )
    (net (code "83") (name "Net-(IC12-OUT)") (class "Default")
      (node (ref "D2") (pin "C") (pinfunction "C_C") (pintype "passive"))
      (node (ref "IC12") (pin "2") (pinfunction "OUT_2") (pintype "output"))
      (node (ref "L2") (pin "1") (pinfunction "1_1") (pintype "passive"))
    )
    (net (code "84") (name "Net-(L_A0-PadA)") (class "Default")
      (node (ref "L_A0") (pin "A") (pinfunction "A_A") (pintype "passive"))
      (node (ref "R5") (pin "2") (pinfunction "2_2") (pintype "bidirectional"))
    )
    (net (code "85") (name "Net-(L_A1-PadA)") (class "Default")
      (node (ref "L_A1") (pin "A") (pinfunction "A_A") (pintype "passive"))
      (node (ref "R6") (pin "2") (pinfunction "2_2") (pintype "bidirectional"))
    )
    (net (code "86") (name "Net-(L_A2-PadA)") (class "Default")
      (node (ref "L_A2") (pin "A") (pinfunction "A_A") (pintype "passive"))
      (node (ref "R7") (pin "2") (pinfunction "2_2") (pintype "bidirectional"))
    )
    (net (code "87") (name "Net-(L_A3-PadA)") (class "Default")
      (node (ref "L_A3") (pin "A") (pinfunction "A_A") (pintype "passive"))
      (node (ref "R8") (pin "2") (pinfunction "2_2") (pintype "bidirectional"))
    )
    (net (code "88") (name "Net-(R9-Pad2)") (class "Default")
      (node (ref "R9") (pin "2") (pinfunction "2_2") (pintype "bidirectional"))
      (node (ref "RUN") (pin "A") (pinfunction "A_A") (pintype "passive"))
    )
    (net (code "89") (name "unconnected-(ARM_MOTE-S-Pad13)") (class "Default")
      (node (ref "ARM_MOT") (pin "13") (pinfunction "S_13") (pintype "passive"))
    )
    (net (code "90") (name "unconnected-(ARM_MOTF-S-Pad14)") (class "Default")
      (node (ref "ARM_MOT") (pin "14") (pinfunction "S_14") (pintype "passive"))
    )
    (net (code "91") (name "unconnected-(ARM_MOTG-S-Pad15)") (class "Default")
      (node (ref "ARM_MOT") (pin "15") (pinfunction "S_15") (pintype "passive"))
    )
    (net (code "92") (name "unconnected-(ARM_MOTH-S-Pad16)") (class "Default")
      (node (ref "ARM_MOT") (pin "16") (pinfunction "S_16") (pintype "passive"))
    )
    (net (code "93") (name "unconnected-(IC1A-R2OUT-Pad9)") (class "Default")
      (node (ref "IC1") (pin "9") (pinfunction "R2OUT_9") (pintype "output"))
    )
    (net (code "94") (name "unconnected-(IC1A-T2OUT-Pad7)") (class "Default")
      (node (ref "IC1") (pin "7") (pinfunction "T2OUT_7") (pintype "output"))
    )
    (net (code "95") (name "unconnected-(IC2-PB4(ADCB4{slash}TMS)-Pad9)") (class "Default")
      (node (ref "IC2") (pin "9") (pinfunction "PB4(ADCB4/TMS)_9") (pintype "bidirectional"))
    )
    (net (code "96") (name "unconnected-(IC2-PB5(ADCB5{slash}TDI)-Pad10)") (class "Default")
      (node (ref "IC2") (pin "10") (pinfunction "PB5(ADCB5/TDI)_10") (pintype "bidirectional"))
    )
    (net (code "97") (name "unconnected-(IC2-PB6(ADCB6{slash}TCK)-Pad11)") (class "Default")
      (node (ref "IC2") (pin "11") (pinfunction "PB6(ADCB6/TCK)_11") (pintype "bidirectional"))
    )
    (net (code "98") (name "unconnected-(IC2-PB7(ADCB7{slash}AC0-OUT{slash}TDO)-Pad12)") (class "Default")
      (node (ref "IC2") (pin "12") (pinfunction "PB7(ADCB7/AC0-OUT/TDO)_12") (pintype "bidirectional"))
    )
    (net (code "99") (name "unconnected-(IC2-PE4(OC1A{slash}~{SS})-Pad39)") (class "Default")
      (node (ref "IC2") (pin "39") (pinfunction "PE4(OC1A/~{SS})_39") (pintype "bidirectional"))
    )
    (net (code "100") (name "unconnected-(IC2-PF0(OC0A{slash}SDA)-Pad45)") (class "Default")
      (node (ref "IC2") (pin "45") (pinfunction "PF0(OC0A/SDA)_45") (pintype "bidirectional"))
    )
    (net (code "101") (name "unconnected-(IC2-PF1(OC0B{slash}XCK0{slash}SCL)-Pad46)") (class "Default")
      (node (ref "IC2") (pin "46") (pinfunction "PF1(OC0B/XCK0/SCL)_46") (pintype "bidirectional"))
    )
    (net (code "102") (name "unconnected-(IC2-PF4(OC1A{slash}~{SS})-Pad49)") (class "Default")
      (node (ref "IC2") (pin "49") (pinfunction "PF4(OC1A/~{SS})_49") (pintype "bidirectional"))
    )
    (net (code "103") (name "unconnected-(IC2-PF5(OC1B{slash}XCK1{slash}MOSI)-Pad50)") (class "Default")
      (node (ref "IC2") (pin "50") (pinfunction "PF5(OC1B/XCK1/MOSI)_50") (pintype "bidirectional"))
    )
    (net (code "104") (name "unconnected-(IC2-PH4(BA0{slash}~{CS0}{slash}A16)-Pad59)") (class "Default")
      (node (ref "IC2") (pin "59") (pinfunction "PH4(BA0/~{CS0}/A16)_59") (pintype "bidirectional"))
    )
    (net (code "105") (name "unconnected-(IC2-PH5(BA1{slash}~{CS1}{slash}A17)-Pad60)") (class "Default")
      (node (ref "IC2") (pin "60") (pinfunction "PH5(BA1/~{CS1}/A17)_60") (pintype "bidirectional"))
    )
    (net (code "106") (name "unconnected-(IC2-PH6(CKE{slash}~{CS2}{slash}A18)-Pad61)") (class "Default")
      (node (ref "IC2") (pin "61") (pinfunction "PH6(CKE/~{CS2}/A18)_61") (pintype "bidirectional"))
    )
    (net (code "107") (name "unconnected-(IC2-PH7(CLK{slash}~{CS3}{slash}A19)-Pad62)") (class "Default")
      (node (ref "IC2") (pin "62") (pinfunction "PH7(CLK/~{CS3}/A19)_62") (pintype "bidirectional"))
    )
    (net (code "108") (name "unconnected-(IC2-PJ0(D0{slash}A0{slash}A8)-Pad65)") (class "Default")
      (node (ref "IC2") (pin "65") (pinfunction "PJ0(D0/A0/A8)_65") (pintype "bidirectional"))
    )
    (net (code "109") (name "unconnected-(IC2-PJ1(D1{slash}A1{slash}A9)-Pad66)") (class "Default")
      (node (ref "IC2") (pin "66") (pinfunction "PJ1(D1/A1/A9)_66") (pintype "bidirectional"))
    )
    (net (code "110") (name "unconnected-(IC2-PJ2(D2{slash}A2{slash}A10)-Pad67)") (class "Default")
      (node (ref "IC2") (pin "67") (pinfunction "PJ2(D2/A2/A10)_67") (pintype "bidirectional"))
    )
    (net (code "111") (name "unconnected-(IC2-PJ3(D3{slash}A3{slash}A11)-Pad68)") (class "Default")
      (node (ref "IC2") (pin "68") (pinfunction "PJ3(D3/A3/A11)_68") (pintype "bidirectional"))
    )
    (net (code "112") (name "unconnected-(IC2-PJ4(A8{slash}D4{slash}A4{slash}A12)-Pad69)") (class "Default")
      (node (ref "IC2") (pin "69") (pinfunction "PJ4(A8/D4/A4/A12)_69") (pintype "bidirectional"))
    )
    (net (code "113") (name "unconnected-(IC2-PJ5(A9{slash}D5{slash}A5{slash}A13)-Pad70)") (class "Default")
      (node (ref "IC2") (pin "70") (pinfunction "PJ5(A9/D5/A5/A13)_70") (pintype "bidirectional"))
    )
    (net (code "114") (name "unconnected-(IC2-PJ6(A10{slash}D6{slash}A6{slash}A14)-Pad71)") (class "Default")
      (node (ref "IC2") (pin "71") (pinfunction "PJ6(A10/D6/A6/A14)_71") (pintype "bidirectional"))
    )
    (net (code "115") (name "unconnected-(IC2-PJ7(A11{slash}D7{slash}A7{slash}A15)-Pad72)") (class "Default")
      (node (ref "IC2") (pin "72") (pinfunction "PJ7(A11/D7/A7/A15)_72") (pintype "bidirectional"))
    )
    (net (code "116") (name "unconnected-(IC2-PK3(A3{slash}A11{slash}A19)-Pad78)") (class "Default")
      (node (ref "IC2") (pin "78") (pinfunction "PK3(A3/A11/A19)_78") (pintype "bidirectional"))
    )
    (net (code "117") (name "unconnected-(IC2-PK4(A4{slash}A12{slash}A20)-Pad79)") (class "Default")
      (node (ref "IC2") (pin "79") (pinfunction "PK4(A4/A12/A20)_79") (pintype "bidirectional"))
    )
    (net (code "118") (name "unconnected-(IC2-PK5(A5{slash}A13{slash}A22)-Pad80)") (class "Default")
      (node (ref "IC2") (pin "80") (pinfunction "PK5(A5/A13/A22)_80") (pintype "bidirectional"))
    )
    (net (code "119") (name "unconnected-(IC2-PK6(A6{slash}A14{slash}A22)-Pad81)") (class "Default")
      (node (ref "IC2") (pin "81") (pinfunction "PK6(A6/A14/A22)_81") (pintype "bidirectional"))
    )
    (net (code "120") (name "unconnected-(IC2-PK7(A7{slash}A15{slash}A23)-Pad82)") (class "Default")
      (node (ref "IC2") (pin "82") (pinfunction "PK7(A7/A15/A23)_82") (pintype "bidirectional"))
    )
    (net (code "121") (name "unconnected-(IC2-PQ1(TOSC2)-Pad86)") (class "Default")
      (node (ref "IC2") (pin "86") (pinfunction "PQ1(TOSC2)_86") (pintype "bidirectional"))
    )
    (net (code "122") (name "unconnected-(IC2-PQ2-Pad87)") (class "Default")
      (node (ref "IC2") (pin "87") (pinfunction "PQ2_87") (pintype "bidirectional"))
    )
    (net (code "123") (name "unconnected-(IC2-PQ3-Pad88)") (class "Default")
      (node (ref "IC2") (pin "88") (pinfunction "PQ3_88") (pintype "bidirectional"))
    )
    (net (code "124") (name "unconnected-(IC6-IO_VCC7-Pad10)") (class "Default")
      (node (ref "IC6") (pin "10") (pinfunction "IO_VCC7_10") (pintype "bidirectional"))
    )
    (net (code "125") (name "unconnected-(PDI_ATMEL-NC-Pad3)") (class "Default")
      (node (ref "PDI_ATMEL") (pin "3") (pinfunction "NC_3") (pintype "passive"))
    )
    (net (code "126") (name "unconnected-(PDI_ATMEL-NC.-Pad4)") (class "Default")
      (node (ref "PDI_ATMEL") (pin "4") (pinfunction "NC._4") (pintype "passive"))
    )
    (net (code "127") (name "unconnected-(UARTA-S-Pad1)") (class "Default")
      (node (ref "UART") (pin "1") (pinfunction "S_1") (pintype "passive"))
    )
  )
)
